# TinyCube10_BetterLib.net
KiCad netlist of a schematic drawn in EAGLE
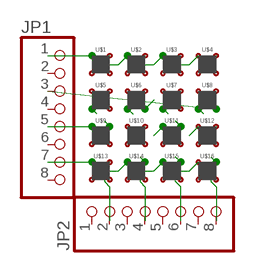
[diagram p0: schematic, sheet 1]

(export (version "E")
  (design (tool "Eeschema 10.0.6"))
  (components
    (comp (ref "JP1")
      (value "PINHD-1X8BIG")
      (footprint "eagle-import:1X08-BIG")
      (libsource (lib "eagle-import") (part "PINHD-1X8BIG"))
    )
    (comp (ref "JP2")
      (value "PINHD-1X8BIG")
      (footprint "eagle-import:1X08-BIG")
      (libsource (lib "eagle-import") (part "PINHD-1X8BIG"))
    )
    (comp (ref "U$1")
      (value "PILLAR")
      (footprint "eagle-import:10MIL")
      (libsource (lib "eagle-import") (part "PILLAR"))
    )
    (comp (ref "U$2")
      (value "PILLAR")
      (footprint "eagle-import:10MIL")
      (libsource (lib "eagle-import") (part "PILLAR"))
    )
    (comp (ref "U$3")
      (value "PILLAR")
      (footprint "eagle-import:10MIL")
      (libsource (lib "eagle-import") (part "PILLAR"))
    )
    (comp (ref "U$4")
      (value "PILLAR")
      (footprint "eagle-import:10MIL")
      (libsource (lib "eagle-import") (part "PILLAR"))
    )
    (comp (ref "U$5")
      (value "PILLAR")
      (footprint "eagle-import:10MIL")
      (libsource (lib "eagle-import") (part "PILLAR"))
    )
    (comp (ref "U$6")
      (value "PILLAR")
      (footprint "eagle-import:10MIL")
      (libsource (lib "eagle-import") (part "PILLAR"))
    )
    (comp (ref "U$7")
      (value "PILLAR")
      (footprint "eagle-import:10MIL")
      (libsource (lib "eagle-import") (part "PILLAR"))
    )
    (comp (ref "U$8")
      (value "PILLAR")
      (footprint "eagle-import:10MIL")
      (libsource (lib "eagle-import") (part "PILLAR"))
    )
    (comp (ref "U$9")
      (value "PILLAR")
      (footprint "eagle-import:10MIL")
      (libsource (lib "eagle-import") (part "PILLAR"))
    )
    (comp (ref "U$10")
      (value "PILLAR")
      (footprint "eagle-import:10MIL")
      (libsource (lib "eagle-import") (part "PILLAR"))
    )
    (comp (ref "U$11")
      (value "PILLAR")
      (footprint "eagle-import:10MIL")
      (libsource (lib "eagle-import") (part "PILLAR"))
    )
    (comp (ref "U$12")
      (value "PILLAR")
      (footprint "eagle-import:10MIL")
      (libsource (lib "eagle-import") (part "PILLAR"))
    )
    (comp (ref "U$13")
      (value "PILLAR")
      (footprint "eagle-import:10MIL")
      (libsource (lib "eagle-import") (part "PILLAR"))
    )
    (comp (ref "U$14")
      (value "PILLAR")
      (footprint "eagle-import:10MIL")
      (libsource (lib "eagle-import") (part "PILLAR"))
    )
    (comp (ref "U$15")
      (value "PILLAR")
      (footprint "eagle-import:10MIL")
      (libsource (lib "eagle-import") (part "PILLAR"))
    )
    (comp (ref "U$16")
      (value "PILLAR")
      (footprint "eagle-import:10MIL")
      (libsource (lib "eagle-import") (part "PILLAR"))
    )
  )
  (nets
    (net (code "1") (name "Net-(JP1-Pad1)") (class "Default")
      (node (ref "JP1") (pin "1") (pinfunction "1_1") (pintype "passive"))
      (node (ref "U$1") (pin "B") (pinfunction "B_B") (pintype "bidirectional"))
      (node (ref "U$2") (pin "B") (pinfunction "B_B") (pintype "bidirectional"))
      (node (ref "U$3") (pin "B") (pinfunction "B_B") (pintype "bidirectional"))
      (node (ref "U$4") (pin "B") (pinfunction "B_B") (pintype "bidirectional"))
    )
    (net (code "2") (name "Net-(JP1-Pad3)") (class "Default")
      (node (ref "JP1") (pin "3") (pinfunction "3_3") (pintype "passive"))
      (node (ref "U$8") (pin "R") (pinfunction "R_R") (pintype "bidirectional"))
    )
    (net (code "3") (name "Net-(JP1-Pad5)") (class "Default")
      (node (ref "JP1") (pin "5") (pinfunction "5_5") (pintype "passive"))
      (node (ref "U$9") (pin "B") (pinfunction "B_B") (pintype "bidirectional"))
    )
    (net (code "4") (name "Net-(JP1-Pad7)") (class "Default")
      (node (ref "JP1") (pin "7") (pinfunction "7_7") (pintype "passive"))
      (node (ref "U$13") (pin "B") (pinfunction "B_B") (pintype "bidirectional"))
      (node (ref "U$14") (pin "B") (pinfunction "B_B") (pintype "bidirectional"))
      (node (ref "U$15") (pin "B") (pinfunction "B_B") (pintype "bidirectional"))
      (node (ref "U$16") (pin "B") (pinfunction "B_B") (pintype "bidirectional"))
    )
    (net (code "5") (name "unconnected-(JP1-Pad2)") (class "Default")
      (node (ref "JP1") (pin "2") (pinfunction "2_2") (pintype "passive"))
    )
    (net (code "6") (name "unconnected-(JP1-Pad4)") (class "Default")
      (node (ref "JP1") (pin "4") (pinfunction "4_4") (pintype "passive"))
    )
    (net (code "7") (name "unconnected-(JP1-Pad6)") (class "Default")
      (node (ref "JP1") (pin "6") (pinfunction "6_6") (pintype "passive"))
    )
    (net (code "8") (name "unconnected-(JP1-Pad8)") (class "Default")
      (node (ref "JP1") (pin "8") (pinfunction "8_8") (pintype "passive"))
    )
    (net (code "9") (name "unconnected-(JP2-Pad1)") (class "Default")
      (node (ref "JP2") (pin "1") (pinfunction "1_1") (pintype "passive"))
    )
    (net (code "10") (name "unconnected-(JP2-Pad2)") (class "Default")
      (node (ref "JP2") (pin "2") (pinfunction "2_2") (pintype "passive"))
    )
    (net (code "11") (name "unconnected-(JP2-Pad3)") (class "Default")
      (node (ref "JP2") (pin "3") (pinfunction "3_3") (pintype "passive"))
    )
    (net (code "12") (name "unconnected-(JP2-Pad4)") (class "Default")
      (node (ref "JP2") (pin "4") (pinfunction "4_4") (pintype "passive"))
    )
    (net (code "13") (name "unconnected-(JP2-Pad5)") (class "Default")
      (node (ref "JP2") (pin "5") (pinfunction "5_5") (pintype "passive"))
    )
    (net (code "14") (name "unconnected-(JP2-Pad6)") (class "Default")
      (node (ref "JP2") (pin "6") (pinfunction "6_6") (pintype "passive"))
    )
    (net (code "15") (name "unconnected-(JP2-Pad7)") (class "Default")
      (node (ref "JP2") (pin "7") (pinfunction "7_7") (pintype "passive"))
    )
    (net (code "16") (name "unconnected-(JP2-Pad8)") (class "Default")
      (node (ref "JP2") (pin "8") (pinfunction "8_8") (pintype "passive"))
    )
    (net (code "17") (name "unconnected-(U$1-PadA)") (class "Default")
      (node (ref "U$1") (pin "A") (pinfunction "A_A") (pintype "bidirectional"))
    )
    (net (code "18") (name "unconnected-(U$1-PadG)") (class "Default")
      (node (ref "U$1") (pin "G") (pinfunction "G_G") (pintype "bidirectional"))
    )
    (net (code "19") (name "unconnected-(U$1-PadR)") (class "Default")
      (node (ref "U$1") (pin "R") (pinfunction "R_R") (pintype "bidirectional"))
    )
    (net (code "20") (name "unconnected-(U$2-PadA)") (class "Default")
      (node (ref "U$2") (pin "A") (pinfunction "A_A") (pintype "bidirectional"))
    )
    (net (code "21") (name "unconnected-(U$2-PadG)") (class "Default")
      (node (ref "U$2") (pin "G") (pinfunction "G_G") (pintype "bidirectional"))
    )
    (net (code "22") (name "unconnected-(U$2-PadR)") (class "Default")
      (node (ref "U$2") (pin "R") (pinfunction "R_R") (pintype "bidirectional"))
    )
    (net (code "23") (name "unconnected-(U$3-PadA)") (class "Default")
      (node (ref "U$3") (pin "A") (pinfunction "A_A") (pintype "bidirectional"))
    )
    (net (code "24") (name "unconnected-(U$3-PadG)") (class "Default")
      (node (ref "U$3") (pin "G") (pinfunction "G_G") (pintype "bidirectional"))
    )
    (net (code "25") (name "unconnected-(U$3-PadR)") (class "Default")
      (node (ref "U$3") (pin "R") (pinfunction "R_R") (pintype "bidirectional"))
    )
    (net (code "26") (name "unconnected-(U$4-PadA)") (class "Default")
      (node (ref "U$4") (pin "A") (pinfunction "A_A") (pintype "bidirectional"))
    )
    (net (code "27") (name "unconnected-(U$4-PadG)") (class "Default")
      (node (ref "U$4") (pin "G") (pinfunction "G_G") (pintype "bidirectional"))
    )
    (net (code "28") (name "unconnected-(U$4-PadR)") (class "Default")
      (node (ref "U$4") (pin "R") (pinfunction "R_R") (pintype "bidirectional"))
    )
    (net (code "29") (name "unconnected-(U$5-PadA)") (class "Default")
      (node (ref "U$5") (pin "A") (pinfunction "A_A") (pintype "bidirectional"))
    )
    (net (code "30") (name "unconnected-(U$5-PadB)") (class "Default")
      (node (ref "U$5") (pin "B") (pinfunction "B_B") (pintype "bidirectional"))
    )
    (net (code "31") (name "unconnected-(U$5-PadG)") (class "Default")
      (node (ref "U$5") (pin "G") (pinfunction "G_G") (pintype "bidirectional"))
    )
    (net (code "32") (name "unconnected-(U$5-PadR)") (class "Default")
      (node (ref "U$5") (pin "R") (pinfunction "R_R") (pintype "bidirectional"))
    )
    (net (code "33") (name "unconnected-(U$6-PadA)") (class "Default")
      (node (ref "U$6") (pin "A") (pinfunction "A_A") (pintype "bidirectional"))
    )
    (net (code "34") (name "unconnected-(U$6-PadB)") (class "Default")
      (node (ref "U$6") (pin "B") (pinfunction "B_B") (pintype "bidirectional"))
    )
    (net (code "35") (name "unconnected-(U$6-PadG)") (class "Default")
      (node (ref "U$6") (pin "G") (pinfunction "G_G") (pintype "bidirectional"))
    )
    (net (code "36") (name "unconnected-(U$6-PadR)") (class "Default")
      (node (ref "U$6") (pin "R") (pinfunction "R_R") (pintype "bidirectional"))
    )
    (net (code "37") (name "unconnected-(U$7-PadA)") (class "Default")
      (node (ref "U$7") (pin "A") (pinfunction "A_A") (pintype "bidirectional"))
    )
    (net (code "38") (name "unconnected-(U$7-PadB)") (class "Default")
      (node (ref "U$7") (pin "B") (pinfunction "B_B") (pintype "bidirectional"))
    )
    (net (code "39") (name "unconnected-(U$7-PadG)") (class "Default")
      (node (ref "U$7") (pin "G") (pinfunction "G_G") (pintype "bidirectional"))
    )
    (net (code "40") (name "unconnected-(U$7-PadR)") (class "Default")
      (node (ref "U$7") (pin "R") (pinfunction "R_R") (pintype "bidirectional"))
    )
    (net (code "41") (name "unconnected-(U$8-PadA)") (class "Default")
      (node (ref "U$8") (pin "A") (pinfunction "A_A") (pintype "bidirectional"))
    )
    (net (code "42") (name "unconnected-(U$8-PadB)") (class "Default")
      (node (ref "U$8") (pin "B") (pinfunction "B_B") (pintype "bidirectional"))
    )
    (net (code "43") (name "unconnected-(U$8-PadG)") (class "Default")
      (node (ref "U$8") (pin "G") (pinfunction "G_G") (pintype "bidirectional"))
    )
    (net (code "44") (name "unconnected-(U$9-PadA)") (class "Default")
      (node (ref "U$9") (pin "A") (pinfunction "A_A") (pintype "bidirectional"))
    )
    (net (code "45") (name "unconnected-(U$9-PadG)") (class "Default")
      (node (ref "U$9") (pin "G") (pinfunction "G_G") (pintype "bidirectional"))
    )
    (net (code "46") (name "unconnected-(U$9-PadR)") (class "Default")
      (node (ref "U$9") (pin "R") (pinfunction "R_R") (pintype "bidirectional"))
    )
    (net (code "47") (name "unconnected-(U$10-PadA)") (class "Default")
      (node (ref "U$10") (pin "A") (pinfunction "A_A") (pintype "bidirectional"))
    )
    (net (code "48") (name "unconnected-(U$10-PadB)") (class "Default")
      (node (ref "U$10") (pin "B") (pinfunction "B_B") (pintype "bidirectional"))
    )
    (net (code "49") (name "unconnected-(U$10-PadG)") (class "Default")
      (node (ref "U$10") (pin "G") (pinfunction "G_G") (pintype "bidirectional"))
    )
    (net (code "50") (name "unconnected-(U$10-PadR)") (class "Default")
      (node (ref "U$10") (pin "R") (pinfunction "R_R") (pintype "bidirectional"))
    )
    (net (code "51") (name "unconnected-(U$11-PadA)") (class "Default")
      (node (ref "U$11") (pin "A") (pinfunction "A_A") (pintype "bidirectional"))
    )
    (net (code "52") (name "unconnected-(U$11-PadB)") (class "Default")
      (node (ref "U$11") (pin "B") (pinfunction "B_B") (pintype "bidirectional"))
    )
    (net (code "53") (name "unconnected-(U$11-PadG)") (class "Default")
      (node (ref "U$11") (pin "G") (pinfunction "G_G") (pintype "bidirectional"))
    )
    (net (code "54") (name "unconnected-(U$11-PadR)") (class "Default")
      (node (ref "U$11") (pin "R") (pinfunction "R_R") (pintype "bidirectional"))
    )
    (net (code "55") (name "unconnected-(U$12-PadA)") (class "Default")
      (node (ref "U$12") (pin "A") (pinfunction "A_A") (pintype "bidirectional"))
    )
    (net (code "56") (name "unconnected-(U$12-PadB)") (class "Default")
      (node (ref "U$12") (pin "B") (pinfunction "B_B") (pintype "bidirectional"))
    )
    (net (code "57") (name "unconnected-(U$12-PadG)") (class "Default")
      (node (ref "U$12") (pin "G") (pinfunction "G_G") (pintype "bidirectional"))
    )
    (net (code "58") (name "unconnected-(U$12-PadR)") (class "Default")
      (node (ref "U$12") (pin "R") (pinfunction "R_R") (pintype "bidirectional"))
    )
    (net (code "59") (name "unconnected-(U$13-PadA)") (class "Default")
      (node (ref "U$13") (pin "A") (pinfunction "A_A") (pintype "bidirectional"))
    )
    (net (code "60") (name "unconnected-(U$13-PadG)") (class "Default")
      (node (ref "U$13") (pin "G") (pinfunction "G_G") (pintype "bidirectional"))
    )
    (net (code "61") (name "unconnected-(U$13-PadR)") (class "Default")
      (node (ref "U$13") (pin "R") (pinfunction "R_R") (pintype "bidirectional"))
    )
    (net (code "62") (name "unconnected-(U$14-PadA)") (class "Default")
      (node (ref "U$14") (pin "A") (pinfunction "A_A") (pintype "bidirectional"))
    )
    (net (code "63") (name "unconnected-(U$14-PadG)") (class "Default")
      (node (ref "U$14") (pin "G") (pinfunction "G_G") (pintype "bidirectional"))
    )
    (net (code "64") (name "unconnected-(U$14-PadR)") (class "Default")
      (node (ref "U$14") (pin "R") (pinfunction "R_R") (pintype "bidirectional"))
    )
    (net (code "65") (name "unconnected-(U$15-PadA)") (class "Default")
      (node (ref "U$15") (pin "A") (pinfunction "A_A") (pintype "bidirectional"))
    )
    (net (code "66") (name "unconnected-(U$15-PadG)") (class "Default")
      (node (ref "U$15") (pin "G") (pinfunction "G_G") (pintype "bidirectional"))
    )
    (net (code "67") (name "unconnected-(U$15-PadR)") (class "Default")
      (node (ref "U$15") (pin "R") (pinfunction "R_R") (pintype "bidirectional"))
    )
    (net (code "68") (name "unconnected-(U$16-PadA)") (class "Default")
      (node (ref "U$16") (pin "A") (pinfunction "A_A") (pintype "bidirectional"))
    )
    (net (code "69") (name "unconnected-(U$16-PadG)") (class "Default")
      (node (ref "U$16") (pin "G") (pinfunction "G_G") (pintype "bidirectional"))
    )
    (net (code "70") (name "unconnected-(U$16-PadR)") (class "Default")
      (node (ref "U$16") (pin "R") (pinfunction "R_R") (pintype "bidirectional"))
    )
  )
)
